# MezzanineConnections.net
KiCad netlist of a schematic drawn in Altium Designer
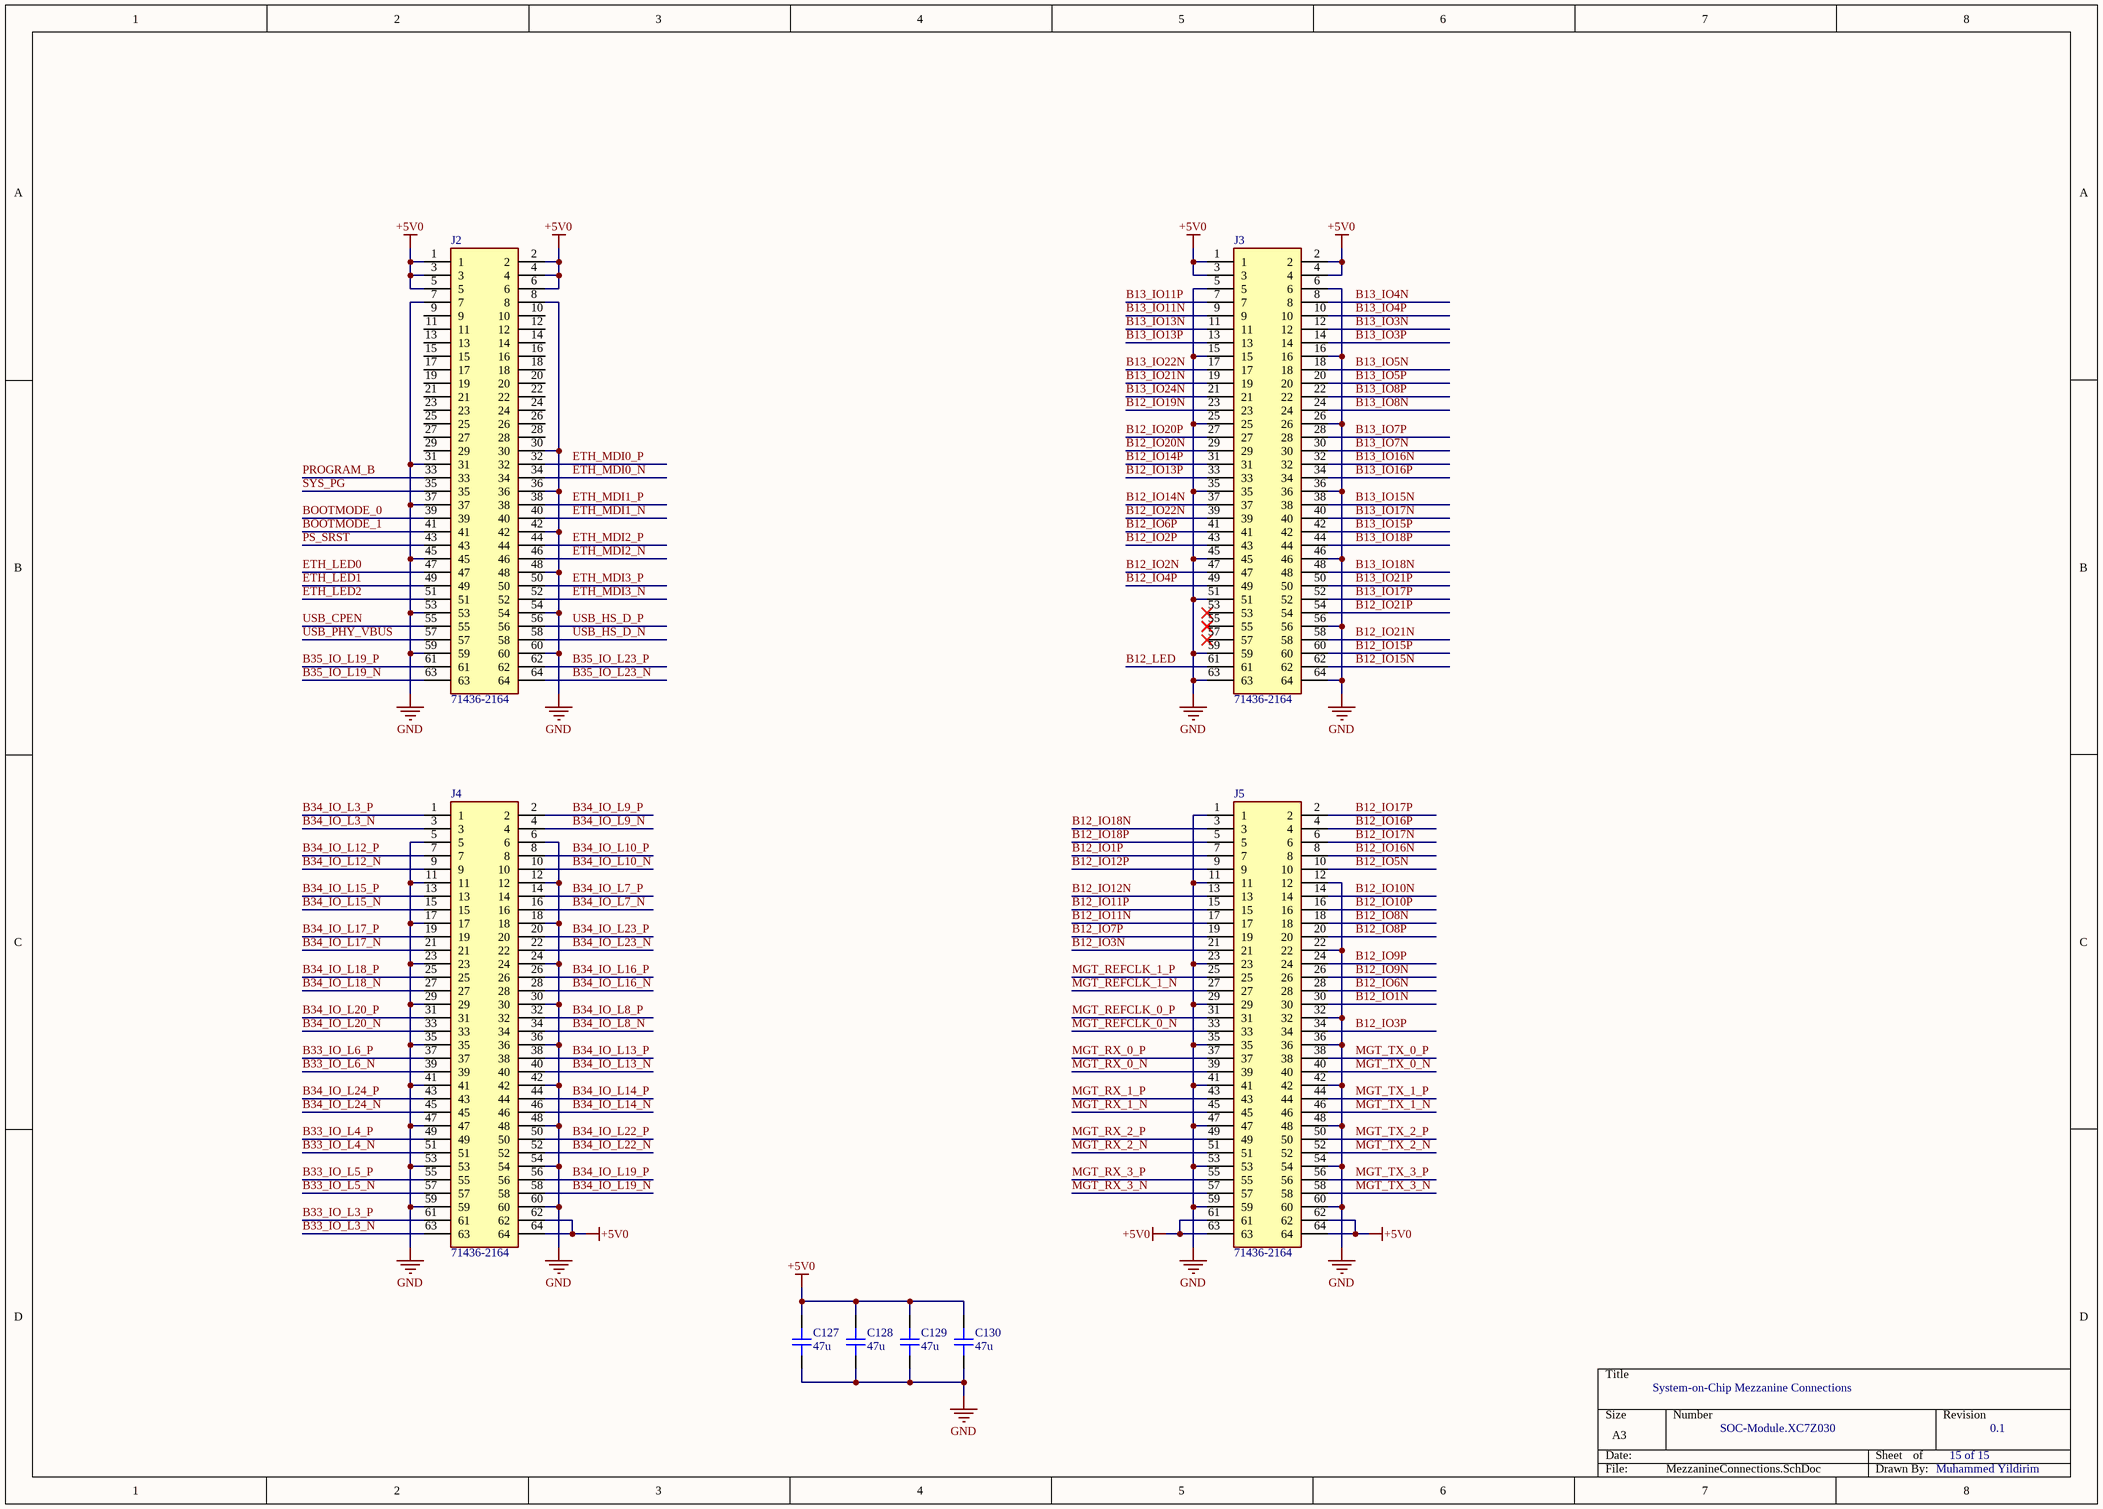
[diagram p0: MezzanineConnections.SchDoc]

(export (version "E")
  (design (tool "Eeschema 10.0.6"))
  (components
    (comp (ref "C127")
      (value "47u")
      (footprint "CAP_0805")
      (description "Capacitor SMD 0805")
      (libsource (lib "Schematic-Lib-PhilsLab") (part "CAP_0805"))
    )
    (comp (ref "C128")
      (value "47u")
      (footprint "CAP_0805")
      (description "Capacitor SMD 0805")
      (libsource (lib "Schematic-Lib-PhilsLab") (part "CAP_0805"))
    )
    (comp (ref "C129")
      (value "47u")
      (footprint "CAP_0805")
      (description "Capacitor SMD 0805")
      (libsource (lib "Schematic-Lib-PhilsLab") (part "CAP_0805"))
    )
    (comp (ref "C130")
      (value "47u")
      (footprint "CAP_0805")
      (description "Capacitor SMD 0805")
      (libsource (lib "Schematic-Lib-PhilsLab") (part "CAP_0805"))
    )
    (comp (ref "J2")
      (value "71436-2164")
      (footprint "714362164")
      (fields (field (name "MOUSER PART NUMBER") "538-71436-2164"))
      (libsource (lib "XC7Z030SCHLib") (part "71436-2164"))
    )
    (comp (ref "J3")
      (value "71436-2164")
      (footprint "714362164")
      (fields (field (name "MOUSER PART NUMBER") "538-71436-2164"))
      (libsource (lib "XC7Z030SCHLib") (part "71436-2164"))
    )
    (comp (ref "J4")
      (value "71436-2164")
      (footprint "714362164")
      (fields (field (name "MOUSER PART NUMBER") "538-71436-2164"))
      (libsource (lib "XC7Z030SCHLib") (part "71436-2164"))
    )
    (comp (ref "J5")
      (value "71436-2164")
      (footprint "714362164")
      (fields (field (name "MOUSER PART NUMBER") "538-71436-2164"))
      (libsource (lib "XC7Z030SCHLib") (part "71436-2164"))
    )
  )
  (nets
    (net (code "1") (name "+5V0") (class "Default")
      (node (ref "C127") (pin "2") (pinfunction "2_2") (pintype "passive"))
      (node (ref "C128") (pin "2") (pinfunction "2_2") (pintype "passive"))
      (node (ref "C129") (pin "2") (pinfunction "2_2") (pintype "passive"))
      (node (ref "C130") (pin "2") (pinfunction "2_2") (pintype "passive"))
      (node (ref "J2") (pin "1") (pinfunction "1_1") (pintype "passive"))
      (node (ref "J2") (pin "2") (pinfunction "2_2") (pintype "passive"))
      (node (ref "J2") (pin "3") (pinfunction "3_3") (pintype "passive"))
      (node (ref "J2") (pin "4") (pinfunction "4_4") (pintype "passive"))
      (node (ref "J2") (pin "5") (pinfunction "5_5") (pintype "passive"))
      (node (ref "J2") (pin "6") (pinfunction "6_6") (pintype "passive"))
      (node (ref "J3") (pin "1") (pinfunction "1_1") (pintype "passive"))
      (node (ref "J3") (pin "2") (pinfunction "2_2") (pintype "passive"))
      (node (ref "J3") (pin "3") (pinfunction "3_3") (pintype "passive"))
      (node (ref "J3") (pin "4") (pinfunction "4_4") (pintype "passive"))
      (node (ref "J4") (pin "62") (pinfunction "62_62") (pintype "passive"))
      (node (ref "J4") (pin "64") (pinfunction "64_64") (pintype "passive"))
      (node (ref "J5") (pin "61") (pinfunction "61_61") (pintype "passive"))
      (node (ref "J5") (pin "62") (pinfunction "62_62") (pintype "passive"))
      (node (ref "J5") (pin "63") (pinfunction "63_63") (pintype "passive"))
      (node (ref "J5") (pin "64") (pinfunction "64_64") (pintype "passive"))
    )
    (net (code "2") (name "/B12_IO1N") (class "Default")
      (node (ref "J5") (pin "30") (pinfunction "30_30") (pintype "passive"))
    )
    (net (code "3") (name "/B12_IO1P") (class "Default")
      (node (ref "J5") (pin "7") (pinfunction "7_7") (pintype "passive"))
    )
    (net (code "4") (name "/B12_IO2N") (class "Default")
      (node (ref "J3") (pin "47") (pinfunction "47_47") (pintype "passive"))
    )
    (net (code "5") (name "/B12_IO2P") (class "Default")
      (node (ref "J3") (pin "43") (pinfunction "43_43") (pintype "passive"))
    )
    (net (code "6") (name "/B12_IO3N") (class "Default")
      (node (ref "J5") (pin "21") (pinfunction "21_21") (pintype "passive"))
    )
    (net (code "7") (name "/B12_IO3P") (class "Default")
      (node (ref "J5") (pin "34") (pinfunction "34_34") (pintype "passive"))
    )
    (net (code "8") (name "/B12_IO4P") (class "Default")
      (node (ref "J3") (pin "49") (pinfunction "49_49") (pintype "passive"))
    )
    (net (code "9") (name "/B12_IO5N") (class "Default")
      (node (ref "J5") (pin "10") (pinfunction "10_10") (pintype "passive"))
    )
    (net (code "10") (name "/B12_IO6N") (class "Default")
      (node (ref "J5") (pin "28") (pinfunction "28_28") (pintype "passive"))
    )
    (net (code "11") (name "/B12_IO6P") (class "Default")
      (node (ref "J3") (pin "41") (pinfunction "41_41") (pintype "passive"))
    )
    (net (code "12") (name "/B12_IO7P") (class "Default")
      (node (ref "J5") (pin "19") (pinfunction "19_19") (pintype "passive"))
    )
    (net (code "13") (name "/B12_IO8N") (class "Default")
      (node (ref "J5") (pin "18") (pinfunction "18_18") (pintype "passive"))
    )
    (net (code "14") (name "/B12_IO8P") (class "Default")
      (node (ref "J5") (pin "20") (pinfunction "20_20") (pintype "passive"))
    )
    (net (code "15") (name "/B12_IO9N") (class "Default")
      (node (ref "J5") (pin "26") (pinfunction "26_26") (pintype "passive"))
    )
    (net (code "16") (name "/B12_IO9P") (class "Default")
      (node (ref "J5") (pin "24") (pinfunction "24_24") (pintype "passive"))
    )
    (net (code "17") (name "/B12_IO10N") (class "Default")
      (node (ref "J5") (pin "14") (pinfunction "14_14") (pintype "passive"))
    )
    (net (code "18") (name "/B12_IO10P") (class "Default")
      (node (ref "J5") (pin "16") (pinfunction "16_16") (pintype "passive"))
    )
    (net (code "19") (name "/B12_IO11N") (class "Default")
      (node (ref "J5") (pin "17") (pinfunction "17_17") (pintype "passive"))
    )
    (net (code "20") (name "/B12_IO11P") (class "Default")
      (node (ref "J5") (pin "15") (pinfunction "15_15") (pintype "passive"))
    )
    (net (code "21") (name "/B12_IO12N") (class "Default")
      (node (ref "J5") (pin "13") (pinfunction "13_13") (pintype "passive"))
    )
    (net (code "22") (name "/B12_IO12P") (class "Default")
      (node (ref "J5") (pin "9") (pinfunction "9_9") (pintype "passive"))
    )
    (net (code "23") (name "/B12_IO13P") (class "Default")
      (node (ref "J3") (pin "33") (pinfunction "33_33") (pintype "passive"))
    )
    (net (code "24") (name "/B12_IO14N") (class "Default")
      (node (ref "J3") (pin "37") (pinfunction "37_37") (pintype "passive"))
    )
    (net (code "25") (name "/B12_IO14P") (class "Default")
      (node (ref "J3") (pin "31") (pinfunction "31_31") (pintype "passive"))
    )
    (net (code "26") (name "/B12_IO15N") (class "Default")
      (node (ref "J3") (pin "62") (pinfunction "62_62") (pintype "passive"))
    )
    (net (code "27") (name "/B12_IO15P") (class "Default")
      (node (ref "J3") (pin "60") (pinfunction "60_60") (pintype "passive"))
    )
    (net (code "28") (name "/B12_IO16N") (class "Default")
      (node (ref "J5") (pin "8") (pinfunction "8_8") (pintype "passive"))
    )
    (net (code "29") (name "/B12_IO16P") (class "Default")
      (node (ref "J5") (pin "4") (pinfunction "4_4") (pintype "passive"))
    )
    (net (code "30") (name "/B12_IO17N") (class "Default")
      (node (ref "J5") (pin "6") (pinfunction "6_6") (pintype "passive"))
    )
    (net (code "31") (name "/B12_IO17P") (class "Default")
      (node (ref "J5") (pin "2") (pinfunction "2_2") (pintype "passive"))
    )
    (net (code "32") (name "/B12_IO18N") (class "Default")
      (node (ref "J5") (pin "3") (pinfunction "3_3") (pintype "passive"))
    )
    (net (code "33") (name "/B12_IO18P") (class "Default")
      (node (ref "J5") (pin "5") (pinfunction "5_5") (pintype "passive"))
    )
    (net (code "34") (name "/B12_IO19N") (class "Default")
      (node (ref "J3") (pin "23") (pinfunction "23_23") (pintype "passive"))
    )
    (net (code "35") (name "/B12_IO20N") (class "Default")
      (node (ref "J3") (pin "29") (pinfunction "29_29") (pintype "passive"))
    )
    (net (code "36") (name "/B12_IO20P") (class "Default")
      (node (ref "J3") (pin "27") (pinfunction "27_27") (pintype "passive"))
    )
    (net (code "37") (name "/B12_IO21N") (class "Default")
      (node (ref "J3") (pin "58") (pinfunction "58_58") (pintype "passive"))
    )
    (net (code "38") (name "/B12_IO21P") (class "Default")
      (node (ref "J3") (pin "54") (pinfunction "54_54") (pintype "passive"))
    )
    (net (code "39") (name "/B12_IO22N") (class "Default")
      (node (ref "J3") (pin "39") (pinfunction "39_39") (pintype "passive"))
    )
    (net (code "40") (name "/B12_LED") (class "Default")
      (node (ref "J3") (pin "61") (pinfunction "61_61") (pintype "passive"))
    )
    (net (code "41") (name "/B13_IO3N") (class "Default")
      (node (ref "J3") (pin "12") (pinfunction "12_12") (pintype "passive"))
    )
    (net (code "42") (name "/B13_IO3P") (class "Default")
      (node (ref "J3") (pin "14") (pinfunction "14_14") (pintype "passive"))
    )
    (net (code "43") (name "/B13_IO4N") (class "Default")
      (node (ref "J3") (pin "8") (pinfunction "8_8") (pintype "passive"))
    )
    (net (code "44") (name "/B13_IO4P") (class "Default")
      (node (ref "J3") (pin "10") (pinfunction "10_10") (pintype "passive"))
    )
    (net (code "45") (name "/B13_IO5N") (class "Default")
      (node (ref "J3") (pin "18") (pinfunction "18_18") (pintype "passive"))
    )
    (net (code "46") (name "/B13_IO5P") (class "Default")
      (node (ref "J3") (pin "20") (pinfunction "20_20") (pintype "passive"))
    )
    (net (code "47") (name "/B13_IO7N") (class "Default")
      (node (ref "J3") (pin "30") (pinfunction "30_30") (pintype "passive"))
    )
    (net (code "48") (name "/B13_IO7P") (class "Default")
      (node (ref "J3") (pin "28") (pinfunction "28_28") (pintype "passive"))
    )
    (net (code "49") (name "/B13_IO8N") (class "Default")
      (node (ref "J3") (pin "24") (pinfunction "24_24") (pintype "passive"))
    )
    (net (code "50") (name "/B13_IO8P") (class "Default")
      (node (ref "J3") (pin "22") (pinfunction "22_22") (pintype "passive"))
    )
    (net (code "51") (name "/B13_IO11N") (class "Default")
      (node (ref "J3") (pin "9") (pinfunction "9_9") (pintype "passive"))
    )
    (net (code "52") (name "/B13_IO11P") (class "Default")
      (node (ref "J3") (pin "7") (pinfunction "7_7") (pintype "passive"))
    )
    (net (code "53") (name "/B13_IO13N") (class "Default")
      (node (ref "J3") (pin "11") (pinfunction "11_11") (pintype "passive"))
    )
    (net (code "54") (name "/B13_IO13P") (class "Default")
      (node (ref "J3") (pin "13") (pinfunction "13_13") (pintype "passive"))
    )
    (net (code "55") (name "/B13_IO15N") (class "Default")
      (node (ref "J3") (pin "38") (pinfunction "38_38") (pintype "passive"))
    )
    (net (code "56") (name "/B13_IO15P") (class "Default")
      (node (ref "J3") (pin "42") (pinfunction "42_42") (pintype "passive"))
    )
    (net (code "57") (name "/B13_IO16N") (class "Default")
      (node (ref "J3") (pin "32") (pinfunction "32_32") (pintype "passive"))
    )
    (net (code "58") (name "/B13_IO16P") (class "Default")
      (node (ref "J3") (pin "34") (pinfunction "34_34") (pintype "passive"))
    )
    (net (code "59") (name "/B13_IO17N") (class "Default")
      (node (ref "J3") (pin "40") (pinfunction "40_40") (pintype "passive"))
    )
    (net (code "60") (name "/B13_IO17P") (class "Default")
      (node (ref "J3") (pin "52") (pinfunction "52_52") (pintype "passive"))
    )
    (net (code "61") (name "/B13_IO18N") (class "Default")
      (node (ref "J3") (pin "48") (pinfunction "48_48") (pintype "passive"))
    )
    (net (code "62") (name "/B13_IO18P") (class "Default")
      (node (ref "J3") (pin "44") (pinfunction "44_44") (pintype "passive"))
    )
    (net (code "63") (name "/B13_IO21N") (class "Default")
      (node (ref "J3") (pin "19") (pinfunction "19_19") (pintype "passive"))
    )
    (net (code "64") (name "/B13_IO21P") (class "Default")
      (node (ref "J3") (pin "50") (pinfunction "50_50") (pintype "passive"))
    )
    (net (code "65") (name "/B13_IO22N") (class "Default")
      (node (ref "J3") (pin "17") (pinfunction "17_17") (pintype "passive"))
    )
    (net (code "66") (name "/B13_IO24N") (class "Default")
      (node (ref "J3") (pin "21") (pinfunction "21_21") (pintype "passive"))
    )
    (net (code "67") (name "/B33_IO_L3_N") (class "Default")
      (node (ref "J4") (pin "63") (pinfunction "63_63") (pintype "passive"))
    )
    (net (code "68") (name "/B33_IO_L3_P") (class "Default")
      (node (ref "J4") (pin "61") (pinfunction "61_61") (pintype "passive"))
    )
    (net (code "69") (name "/B33_IO_L4_N") (class "Default")
      (node (ref "J4") (pin "51") (pinfunction "51_51") (pintype "passive"))
    )
    (net (code "70") (name "/B33_IO_L4_P") (class "Default")
      (node (ref "J4") (pin "49") (pinfunction "49_49") (pintype "passive"))
    )
    (net (code "71") (name "/B33_IO_L5_N") (class "Default")
      (node (ref "J4") (pin "57") (pinfunction "57_57") (pintype "passive"))
    )
    (net (code "72") (name "/B33_IO_L5_P") (class "Default")
      (node (ref "J4") (pin "55") (pinfunction "55_55") (pintype "passive"))
    )
    (net (code "73") (name "/B33_IO_L6_N") (class "Default")
      (node (ref "J4") (pin "39") (pinfunction "39_39") (pintype "passive"))
    )
    (net (code "74") (name "/B33_IO_L6_P") (class "Default")
      (node (ref "J4") (pin "37") (pinfunction "37_37") (pintype "passive"))
    )
    (net (code "75") (name "/B34_IO_L3_N") (class "Default")
      (node (ref "J4") (pin "3") (pinfunction "3_3") (pintype "passive"))
    )
    (net (code "76") (name "/B34_IO_L3_P") (class "Default")
      (node (ref "J4") (pin "1") (pinfunction "1_1") (pintype "passive"))
    )
    (net (code "77") (name "/B34_IO_L7_N") (class "Default")
      (node (ref "J4") (pin "16") (pinfunction "16_16") (pintype "passive"))
    )
    (net (code "78") (name "/B34_IO_L7_P") (class "Default")
      (node (ref "J4") (pin "14") (pinfunction "14_14") (pintype "passive"))
    )
    (net (code "79") (name "/B34_IO_L8_N") (class "Default")
      (node (ref "J4") (pin "34") (pinfunction "34_34") (pintype "passive"))
    )
    (net (code "80") (name "/B34_IO_L8_P") (class "Default")
      (node (ref "J4") (pin "32") (pinfunction "32_32") (pintype "passive"))
    )
    (net (code "81") (name "/B34_IO_L9_N") (class "Default")
      (node (ref "J4") (pin "4") (pinfunction "4_4") (pintype "passive"))
    )
    (net (code "82") (name "/B34_IO_L9_P") (class "Default")
      (node (ref "J4") (pin "2") (pinfunction "2_2") (pintype "passive"))
    )
    (net (code "83") (name "/B34_IO_L10_N") (class "Default")
      (node (ref "J4") (pin "10") (pinfunction "10_10") (pintype "passive"))
    )
    (net (code "84") (name "/B34_IO_L10_P") (class "Default")
      (node (ref "J4") (pin "8") (pinfunction "8_8") (pintype "passive"))
    )
    (net (code "85") (name "/B34_IO_L12_N") (class "Default")
      (node (ref "J4") (pin "9") (pinfunction "9_9") (pintype "passive"))
    )
    (net (code "86") (name "/B34_IO_L12_P") (class "Default")
      (node (ref "J4") (pin "7") (pinfunction "7_7") (pintype "passive"))
    )
    (net (code "87") (name "/B34_IO_L13_N") (class "Default")
      (node (ref "J4") (pin "40") (pinfunction "40_40") (pintype "passive"))
    )
    (net (code "88") (name "/B34_IO_L13_P") (class "Default")
      (node (ref "J4") (pin "38") (pinfunction "38_38") (pintype "passive"))
    )
    (net (code "89") (name "/B34_IO_L14_N") (class "Default")
      (node (ref "J4") (pin "46") (pinfunction "46_46") (pintype "passive"))
    )
    (net (code "90") (name "/B34_IO_L14_P") (class "Default")
      (node (ref "J4") (pin "44") (pinfunction "44_44") (pintype "passive"))
    )
    (net (code "91") (name "/B34_IO_L15_N") (class "Default")
      (node (ref "J4") (pin "15") (pinfunction "15_15") (pintype "passive"))
    )
    (net (code "92") (name "/B34_IO_L15_P") (class "Default")
      (node (ref "J4") (pin "13") (pinfunction "13_13") (pintype "passive"))
    )
    (net (code "93") (name "/B34_IO_L16_N") (class "Default")
      (node (ref "J4") (pin "28") (pinfunction "28_28") (pintype "passive"))
    )
    (net (code "94") (name "/B34_IO_L16_P") (class "Default")
      (node (ref "J4") (pin "26") (pinfunction "26_26") (pintype "passive"))
    )
    (net (code "95") (name "/B34_IO_L17_N") (class "Default")
      (node (ref "J4") (pin "21") (pinfunction "21_21") (pintype "passive"))
    )
    (net (code "96") (name "/B34_IO_L17_P") (class "Default")
      (node (ref "J4") (pin "19") (pinfunction "19_19") (pintype "passive"))
    )
    (net (code "97") (name "/B34_IO_L18_N") (class "Default")
      (node (ref "J4") (pin "27") (pinfunction "27_27") (pintype "passive"))
    )
    (net (code "98") (name "/B34_IO_L18_P") (class "Default")
      (node (ref "J4") (pin "25") (pinfunction "25_25") (pintype "passive"))
    )
    (net (code "99") (name "/B34_IO_L19_N") (class "Default")
      (node (ref "J4") (pin "58") (pinfunction "58_58") (pintype "passive"))
    )
    (net (code "100") (name "/B34_IO_L19_P") (class "Default")
      (node (ref "J4") (pin "56") (pinfunction "56_56") (pintype "passive"))
    )
    (net (code "101") (name "/B34_IO_L20_N") (class "Default")
      (node (ref "J4") (pin "33") (pinfunction "33_33") (pintype "passive"))
    )
    (net (code "102") (name "/B34_IO_L20_P") (class "Default")
      (node (ref "J4") (pin "31") (pinfunction "31_31") (pintype "passive"))
    )
    (net (code "103") (name "/B34_IO_L22_N") (class "Default")
      (node (ref "J4") (pin "52") (pinfunction "52_52") (pintype "passive"))
    )
    (net (code "104") (name "/B34_IO_L22_P") (class "Default")
      (node (ref "J4") (pin "50") (pinfunction "50_50") (pintype "passive"))
    )
    (net (code "105") (name "/B34_IO_L23_N") (class "Default")
      (node (ref "J4") (pin "22") (pinfunction "22_22") (pintype "passive"))
    )
    (net (code "106") (name "/B34_IO_L23_P") (class "Default")
      (node (ref "J4") (pin "20") (pinfunction "20_20") (pintype "passive"))
    )
    (net (code "107") (name "/B34_IO_L24_N") (class "Default")
      (node (ref "J4") (pin "45") (pinfunction "45_45") (pintype "passive"))
    )
    (net (code "108") (name "/B34_IO_L24_P") (class "Default")
      (node (ref "J4") (pin "43") (pinfunction "43_43") (pintype "passive"))
    )
    (net (code "109") (name "/B35_IO_L19_N") (class "Default")
      (node (ref "J2") (pin "63") (pinfunction "63_63") (pintype "passive"))
    )
    (net (code "110") (name "/B35_IO_L19_P") (class "Default")
      (node (ref "J2") (pin "61") (pinfunction "61_61") (pintype "passive"))
    )
    (net (code "111") (name "/B35_IO_L23_N") (class "Default")
      (node (ref "J2") (pin "64") (pinfunction "64_64") (pintype "passive"))
    )
    (net (code "112") (name "/B35_IO_L23_P") (class "Default")
      (node (ref "J2") (pin "62") (pinfunction "62_62") (pintype "passive"))
    )
    (net (code "113") (name "/BOOTMODE_0") (class "Default")
      (node (ref "J2") (pin "39") (pinfunction "39_39") (pintype "passive"))
    )
    (net (code "114") (name "/BOOTMODE_1") (class "Default")
      (node (ref "J2") (pin "41") (pinfunction "41_41") (pintype "passive"))
    )
    (net (code "115") (name "/ETH_LED0") (class "Default")
      (node (ref "J2") (pin "47") (pinfunction "47_47") (pintype "passive"))
    )
    (net (code "116") (name "/ETH_LED1") (class "Default")
      (node (ref "J2") (pin "49") (pinfunction "49_49") (pintype "passive"))
    )
    (net (code "117") (name "/ETH_LED2") (class "Default")
      (node (ref "J2") (pin "51") (pinfunction "51_51") (pintype "passive"))
    )
    (net (code "118") (name "/ETH_MDI0_N") (class "Default")
      (node (ref "J2") (pin "34") (pinfunction "34_34") (pintype "passive"))
    )
    (net (code "119") (name "/ETH_MDI0_P") (class "Default")
      (node (ref "J2") (pin "32") (pinfunction "32_32") (pintype "passive"))
    )
    (net (code "120") (name "/ETH_MDI1_N") (class "Default")
      (node (ref "J2") (pin "40") (pinfunction "40_40") (pintype "passive"))
    )
    (net (code "121") (name "/ETH_MDI1_P") (class "Default")
      (node (ref "J2") (pin "38") (pinfunction "38_38") (pintype "passive"))
    )
    (net (code "122") (name "/ETH_MDI2_N") (class "Default")
      (node (ref "J2") (pin "46") (pinfunction "46_46") (pintype "passive"))
    )
    (net (code "123") (name "/ETH_MDI2_P") (class "Default")
      (node (ref "J2") (pin "44") (pinfunction "44_44") (pintype "passive"))
    )
    (net (code "124") (name "/ETH_MDI3_N") (class "Default")
      (node (ref "J2") (pin "52") (pinfunction "52_52") (pintype "passive"))
    )
    (net (code "125") (name "/ETH_MDI3_P") (class "Default")
      (node (ref "J2") (pin "50") (pinfunction "50_50") (pintype "passive"))
    )
    (net (code "126") (name "/MGT_REFCLK_0_N") (class "Default")
      (node (ref "J5") (pin "33") (pinfunction "33_33") (pintype "passive"))
    )
    (net (code "127") (name "/MGT_REFCLK_0_P") (class "Default")
      (node (ref "J5") (pin "31") (pinfunction "31_31") (pintype "passive"))
    )
    (net (code "128") (name "/MGT_REFCLK_1_N") (class "Default")
      (node (ref "J5") (pin "27") (pinfunction "27_27") (pintype "passive"))
    )
    (net (code "129") (name "/MGT_REFCLK_1_P") (class "Default")
      (node (ref "J5") (pin "25") (pinfunction "25_25") (pintype "passive"))
    )
    (net (code "130") (name "/MGT_RX_0_N") (class "Default")
      (node (ref "J5") (pin "39") (pinfunction "39_39") (pintype "passive"))
    )
    (net (code "131") (name "/MGT_RX_0_P") (class "Default")
      (node (ref "J5") (pin "37") (pinfunction "37_37") (pintype "passive"))
    )
    (net (code "132") (name "/MGT_RX_1_N") (class "Default")
      (node (ref "J5") (pin "45") (pinfunction "45_45") (pintype "passive"))
    )
    (net (code "133") (name "/MGT_RX_1_P") (class "Default")
      (node (ref "J5") (pin "43") (pinfunction "43_43") (pintype "passive"))
    )
    (net (code "134") (name "/MGT_RX_2_N") (class "Default")
      (node (ref "J5") (pin "51") (pinfunction "51_51") (pintype "passive"))
    )
    (net (code "135") (name "/MGT_RX_2_P") (class "Default")
      (node (ref "J5") (pin "49") (pinfunction "49_49") (pintype "passive"))
    )
    (net (code "136") (name "/MGT_RX_3_N") (class "Default")
      (node (ref "J5") (pin "57") (pinfunction "57_57") (pintype "passive"))
    )
    (net (code "137") (name "/MGT_RX_3_P") (class "Default")
      (node (ref "J5") (pin "55") (pinfunction "55_55") (pintype "passive"))
    )
    (net (code "138") (name "/MGT_TX_0_N") (class "Default")
      (node (ref "J5") (pin "40") (pinfunction "40_40") (pintype "passive"))
    )
    (net (code "139") (name "/MGT_TX_0_P") (class "Default")
      (node (ref "J5") (pin "38") (pinfunction "38_38") (pintype "passive"))
    )
    (net (code "140") (name "/MGT_TX_1_N") (class "Default")
      (node (ref "J5") (pin "46") (pinfunction "46_46") (pintype "passive"))
    )
    (net (code "141") (name "/MGT_TX_1_P") (class "Default")
      (node (ref "J5") (pin "44") (pinfunction "44_44") (pintype "passive"))
    )
    (net (code "142") (name "/MGT_TX_2_N") (class "Default")
      (node (ref "J5") (pin "52") (pinfunction "52_52") (pintype "passive"))
    )
    (net (code "143") (name "/MGT_TX_2_P") (class "Default")
      (node (ref "J5") (pin "50") (pinfunction "50_50") (pintype "passive"))
    )
    (net (code "144") (name "/MGT_TX_3_N") (class "Default")
      (node (ref "J5") (pin "58") (pinfunction "58_58") (pintype "passive"))
    )
    (net (code "145") (name "/MGT_TX_3_P") (class "Default")
      (node (ref "J5") (pin "56") (pinfunction "56_56") (pintype "passive"))
    )
    (net (code "146") (name "/PROGRAM_B") (class "Default")
      (node (ref "J2") (pin "33") (pinfunction "33_33") (pintype "passive"))
    )
    (net (code "147") (name "/PS_SRST") (class "Default")
      (node (ref "J2") (pin "43") (pinfunction "43_43") (pintype "passive"))
    )
    (net (code "148") (name "/SYS_PG") (class "Default")
      (node (ref "J2") (pin "35") (pinfunction "35_35") (pintype "passive"))
    )
    (net (code "149") (name "/USB_CPEN") (class "Default")
      (node (ref "J2") (pin "55") (pinfunction "55_55") (pintype "passive"))
    )
    (net (code "150") (name "/USB_HS_D_N") (class "Default")
      (node (ref "J2") (pin "58") (pinfunction "58_58") (pintype "passive"))
    )
    (net (code "151") (name "/USB_HS_D_P") (class "Default")
      (node (ref "J2") (pin "56") (pinfunction "56_56") (pintype "passive"))
    )
    (net (code "152") (name "/USB_PHY_VBUS") (class "Default")
      (node (ref "J2") (pin "57") (pinfunction "57_57") (pintype "passive"))
    )
    (net (code "153") (name "GND") (class "Default")
      (node (ref "C127") (pin "1") (pinfunction "1_1") (pintype "passive"))
      (node (ref "C128") (pin "1") (pinfunction "1_1") (pintype "passive"))
      (node (ref "C129") (pin "1") (pinfunction "1_1") (pintype "passive"))
      (node (ref "C130") (pin "1") (pinfunction "1_1") (pintype "passive"))
      (node (ref "J2") (pin "30") (pinfunction "30_30") (pintype "passive"))
      (node (ref "J2") (pin "31") (pinfunction "31_31") (pintype "passive"))
      (node (ref "J2") (pin "36") (pinfunction "36_36") (pintype "passive"))
      (node (ref "J2") (pin "37") (pinfunction "37_37") (pintype "passive"))
      (node (ref "J2") (pin "42") (pinfunction "42_42") (pintype "passive"))
      (node (ref "J2") (pin "45") (pinfunction "45_45") (pintype "passive"))
      (node (ref "J2") (pin "48") (pinfunction "48_48") (pintype "passive"))
      (node (ref "J2") (pin "53") (pinfunction "53_53") (pintype "passive"))
      (node (ref "J2") (pin "54") (pinfunction "54_54") (pintype "passive"))
      (node (ref "J2") (pin "59") (pinfunction "59_59") (pintype "passive"))
      (node (ref "J2") (pin "60") (pinfunction "60_60") (pintype "passive"))
      (node (ref "J2") (pin "7") (pinfunction "7_7") (pintype "passive"))
      (node (ref "J2") (pin "8") (pinfunction "8_8") (pintype "passive"))
      (node (ref "J3") (pin "15") (pinfunction "15_15") (pintype "passive"))
      (node (ref "J3") (pin "16") (pinfunction "16_16") (pintype "passive"))
      (node (ref "J3") (pin "25") (pinfunction "25_25") (pintype "passive"))
      (node (ref "J3") (pin "26") (pinfunction "26_26") (pintype "passive"))
      (node (ref "J3") (pin "35") (pinfunction "35_35") (pintype "passive"))
      (node (ref "J3") (pin "36") (pinfunction "36_36") (pintype "passive"))
      (node (ref "J3") (pin "45") (pinfunction "45_45") (pintype "passive"))
      (node (ref "J3") (pin "46") (pinfunction "46_46") (pintype "passive"))
      (node (ref "J3") (pin "5") (pinfunction "5_5") (pintype "passive"))
      (node (ref "J3") (pin "51") (pinfunction "51_51") (pintype "passive"))
      (node (ref "J3") (pin "56") (pinfunction "56_56") (pintype "passive"))
      (node (ref "J3") (pin "59") (pinfunction "59_59") (pintype "passive"))
      (node (ref "J3") (pin "6") (pinfunction "6_6") (pintype "passive"))
      (node (ref "J3") (pin "63") (pinfunction "63_63") (pintype "passive"))
      (node (ref "J3") (pin "64") (pinfunction "64_64") (pintype "passive"))
      (node (ref "J4") (pin "11") (pinfunction "11_11") (pintype "passive"))
      (node (ref "J4") (pin "12") (pinfunction "12_12") (pintype "passive"))
      (node (ref "J4") (pin "17") (pinfunction "17_17") (pintype "passive"))
      (node (ref "J4") (pin "18") (pinfunction "18_18") (pintype "passive"))
      (node (ref "J4") (pin "23") (pinfunction "23_23") (pintype "passive"))
      (node (ref "J4") (pin "24") (pinfunction "24_24") (pintype "passive"))
      (node (ref "J4") (pin "29") (pinfunction "29_29") (pintype "passive"))
      (node (ref "J4") (pin "30") (pinfunction "30_30") (pintype "passive"))
      (node (ref "J4") (pin "35") (pinfunction "35_35") (pintype "passive"))
      (node (ref "J4") (pin "36") (pinfunction "36_36") (pintype "passive"))
      (node (ref "J4") (pin "41") (pinfunction "41_41") (pintype "passive"))
      (node (ref "J4") (pin "42") (pinfunction "42_42") (pintype "passive"))
      (node (ref "J4") (pin "47") (pinfunction "47_47") (pintype "passive"))
      (node (ref "J4") (pin "48") (pinfunction "48_48") (pintype "passive"))
      (node (ref "J4") (pin "5") (pinfunction "5_5") (pintype "passive"))
      (node (ref "J4") (pin "53") (pinfunction "53_53") (pintype "passive"))
      (node (ref "J4") (pin "54") (pinfunction "54_54") (pintype "passive"))
      (node (ref "J4") (pin "59") (pinfunction "59_59") (pintype "passive"))
      (node (ref "J4") (pin "6") (pinfunction "6_6") (pintype "passive"))
      (node (ref "J4") (pin "60") (pinfunction "60_60") (pintype "passive"))
      (node (ref "J5") (pin "1") (pinfunction "1_1") (pintype "passive"))
      (node (ref "J5") (pin "11") (pinfunction "11_11") (pintype "passive"))
      (node (ref "J5") (pin "12") (pinfunction "12_12") (pintype "passive"))
      (node (ref "J5") (pin "22") (pinfunction "22_22") (pintype "passive"))
      (node (ref "J5") (pin "23") (pinfunction "23_23") (pintype "passive"))
      (node (ref "J5") (pin "29") (pinfunction "29_29") (pintype "passive"))
      (node (ref "J5") (pin "32") (pinfunction "32_32") (pintype "passive"))
      (node (ref "J5") (pin "35") (pinfunction "35_35") (pintype "passive"))
      (node (ref "J5") (pin "36") (pinfunction "36_36") (pintype "passive"))
      (node (ref "J5") (pin "41") (pinfunction "41_41") (pintype "passive"))
      (node (ref "J5") (pin "42") (pinfunction "42_42") (pintype "passive"))
      (node (ref "J5") (pin "47") (pinfunction "47_47") (pintype "passive"))
      (node (ref "J5") (pin "48") (pinfunction "48_48") (pintype "passive"))
      (node (ref "J5") (pin "53") (pinfunction "53_53") (pintype "passive"))
      (node (ref "J5") (pin "54") (pinfunction "54_54") (pintype "passive"))
      (node (ref "J5") (pin "59") (pinfunction "59_59") (pintype "passive"))
      (node (ref "J5") (pin "60") (pinfunction "60_60") (pintype "passive"))
    )
    (net (code "154") (name "unconnected-(J2-Pad9)") (class "Default")
      (node (ref "J2") (pin "9") (pinfunction "9_9") (pintype "passive"))
    )
    (net (code "155") (name "unconnected-(J2-Pad10)") (class "Default")
      (node (ref "J2") (pin "10") (pinfunction "10_10") (pintype "passive"))
    )
    (net (code "156") (name "unconnected-(J2-Pad11)") (class "Default")
      (node (ref "J2") (pin "11") (pinfunction "11_11") (pintype "passive"))
    )
    (net (code "157") (name "unconnected-(J2-Pad12)") (class "Default")
      (node (ref "J2") (pin "12") (pinfunction "12_12") (pintype "passive"))
    )
    (net (code "158") (name "unconnected-(J2-Pad13)") (class "Default")
      (node (ref "J2") (pin "13") (pinfunction "13_13") (pintype "passive"))
    )
    (net (code "159") (name "unconnected-(J2-Pad14)") (class "Default")
      (node (ref "J2") (pin "14") (pinfunction "14_14") (pintype "passive"))
    )
    (net (code "160") (name "unconnected-(J2-Pad15)") (class "Default")
      (node (ref "J2") (pin "15") (pinfunction "15_15") (pintype "passive"))
    )
    (net (code "161") (name "unconnected-(J2-Pad16)") (class "Default")
      (node (ref "J2") (pin "16") (pinfunction "16_16") (pintype "passive"))
    )
    (net (code "162") (name "unconnected-(J2-Pad17)") (class "Default")
      (node (ref "J2") (pin "17") (pinfunction "17_17") (pintype "passive"))
    )
    (net (code "163") (name "unconnected-(J2-Pad18)") (class "Default")
      (node (ref "J2") (pin "18") (pinfunction "18_18") (pintype "passive"))
    )
    (net (code "164") (name "unconnected-(J2-Pad19)") (class "Default")
      (node (ref "J2") (pin "19") (pinfunction "19_19") (pintype "passive"))
    )
    (net (code "165") (name "unconnected-(J2-Pad20)") (class "Default")
      (node (ref "J2") (pin "20") (pinfunction "20_20") (pintype "passive"))
    )
    (net (code "166") (name "unconnected-(J2-Pad21)") (class "Default")
      (node (ref "J2") (pin "21") (pinfunction "21_21") (pintype "passive"))
    )
    (net (code "167") (name "unconnected-(J2-Pad22)") (class "Default")
      (node (ref "J2") (pin "22") (pinfunction "22_22") (pintype "passive"))
    )
    (net (code "168") (name "unconnected-(J2-Pad23)") (class "Default")
      (node (ref "J2") (pin "23") (pinfunction "23_23") (pintype "passive"))
    )
    (net (code "169") (name "unconnected-(J2-Pad24)") (class "Default")
      (node (ref "J2") (pin "24") (pinfunction "24_24") (pintype "passive"))
    )
    (net (code "170") (name "unconnected-(J2-Pad25)") (class "Default")
      (node (ref "J2") (pin "25") (pinfunction "25_25") (pintype "passive"))
    )
    (net (code "171") (name "unconnected-(J2-Pad26)") (class "Default")
      (node (ref "J2") (pin "26") (pinfunction "26_26") (pintype "passive"))
    )
    (net (code "172") (name "unconnected-(J2-Pad27)") (class "Default")
      (node (ref "J2") (pin "27") (pinfunction "27_27") (pintype "passive"))
    )
    (net (code "173") (name "unconnected-(J2-Pad28)") (class "Default")
      (node (ref "J2") (pin "28") (pinfunction "28_28") (pintype "passive"))
    )
    (net (code "174") (name "unconnected-(J2-Pad29)") (class "Default")
      (node (ref "J2") (pin "29") (pinfunction "29_29") (pintype "passive"))
    )
    (net (code "175") (name "unconnected-(J3-Pad53)") (class "Default")
      (node (ref "J3") (pin "53") (pinfunction "53_53") (pintype "passive+no_connect"))
    )
    (net (code "176") (name "unconnected-(J3-Pad55)") (class "Default")
      (node (ref "J3") (pin "55") (pinfunction "55_55") (pintype "passive+no_connect"))
    )
    (net (code "177") (name "unconnected-(J3-Pad57)") (class "Default")
      (node (ref "J3") (pin "57") (pinfunction "57_57") (pintype "passive+no_connect"))
    )
  )
)
